# Moving_balls.net
KiCad netlist of a schematic drawn in Altium Designer
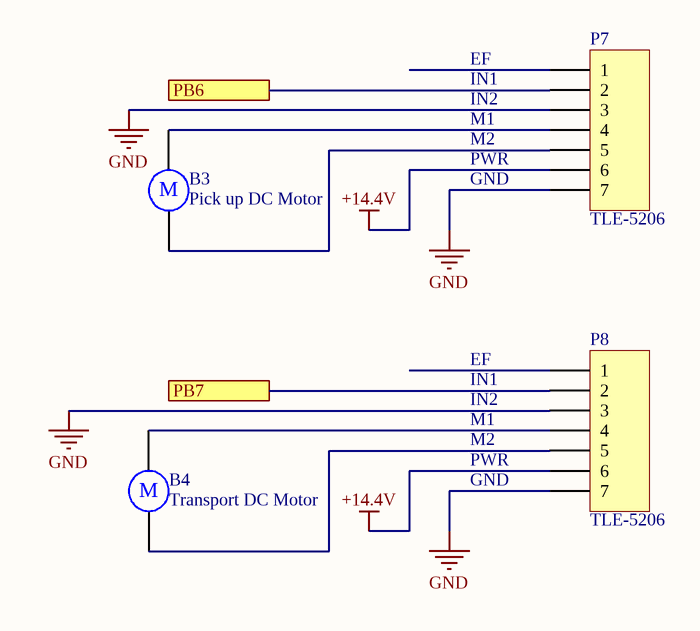
[diagram p0: Moving_balls.SchDoc]

(export (version "E")
  (design (tool "Eeschema 10.0.6"))
  (components
    (comp (ref "B3")
      (value "Pick up DC Motor")
      (footprint "RB5-10.5")
      (description "Motor, General Kind")
      (fields (field (name "MANUFACTURER") "Generic Components"))
      (libsource (lib "ME218_BaseLib") (part "Motor"))
    )
    (comp (ref "B4")
      (value "Transport DC Motor")
      (footprint "RB5-10.5")
      (description "Motor, General Kind")
      (fields (field (name "MANUFACTURER") "Generic Components"))
      (libsource (lib "ME218_BaseLib") (part "Motor"))
    )
    (comp (ref "P7")
      (value "TLE-5206")
      (footprint "HDR1X7")
      (description "Header, 7-Pin")
      (fields (field (name "PUBLISHER") "Altium Limited"))
      (libsource (lib "Miscellaneous Connectors") (part "Header 7"))
    )
    (comp (ref "P8")
      (value "TLE-5206")
      (footprint "HDR1X7")
      (description "Header, 7-Pin")
      (fields (field (name "PUBLISHER") "Altium Limited"))
      (libsource (lib "Miscellaneous Connectors") (part "Header 7"))
    )
  )
  (nets
    (net (code "1") (name "+14.4V") (class "Default")
      (node (ref "P7") (pin "6") (pinfunction "6_6") (pintype "passive"))
      (node (ref "P8") (pin "6") (pinfunction "6_6") (pintype "passive"))
    )
    (net (code "2") (name "/PB6") (class "Default")
      (node (ref "P7") (pin "2") (pinfunction "2_2") (pintype "passive"))
    )
    (net (code "3") (name "/PB7") (class "Default")
      (node (ref "P8") (pin "2") (pinfunction "2_2") (pintype "passive"))
    )
    (net (code "4") (name "GND") (class "Default")
      (node (ref "P7") (pin "3") (pinfunction "3_3") (pintype "passive"))
      (node (ref "P7") (pin "7") (pinfunction "7_7") (pintype "passive"))
      (node (ref "P8") (pin "3") (pinfunction "3_3") (pintype "passive"))
      (node (ref "P8") (pin "7") (pinfunction "7_7") (pintype "passive"))
    )
    (net (code "5") (name "Net-(B3-Pad1)") (class "Default")
      (node (ref "B3") (pin "1") (pinfunction "1_1") (pintype "passive"))
      (node (ref "P7") (pin "4") (pinfunction "4_4") (pintype "passive"))
    )
    (net (code "6") (name "Net-(B3-Pad2)") (class "Default")
      (node (ref "B3") (pin "2") (pinfunction "2_2") (pintype "passive"))
      (node (ref "P7") (pin "5") (pinfunction "5_5") (pintype "passive"))
    )
    (net (code "7") (name "Net-(B4-Pad1)") (class "Default")
      (node (ref "B4") (pin "1") (pinfunction "1_1") (pintype "passive"))
      (node (ref "P8") (pin "4") (pinfunction "4_4") (pintype "passive"))
    )
    (net (code "8") (name "Net-(B4-Pad2)") (class "Default")
      (node (ref "B4") (pin "2") (pinfunction "2_2") (pintype "passive"))
      (node (ref "P8") (pin "5") (pinfunction "5_5") (pintype "passive"))
    )
    (net (code "9") (name "unconnected-(P7-Pad1)") (class "Default")
      (node (ref "P7") (pin "1") (pinfunction "1_1") (pintype "passive"))
    )
    (net (code "10") (name "unconnected-(P8-Pad1)") (class "Default")
      (node (ref "P8") (pin "1") (pinfunction "1_1") (pintype "passive"))
    )
  )
)
